# micro_schematic.net
KiCad netlist of a schematic drawn in Altium Designer
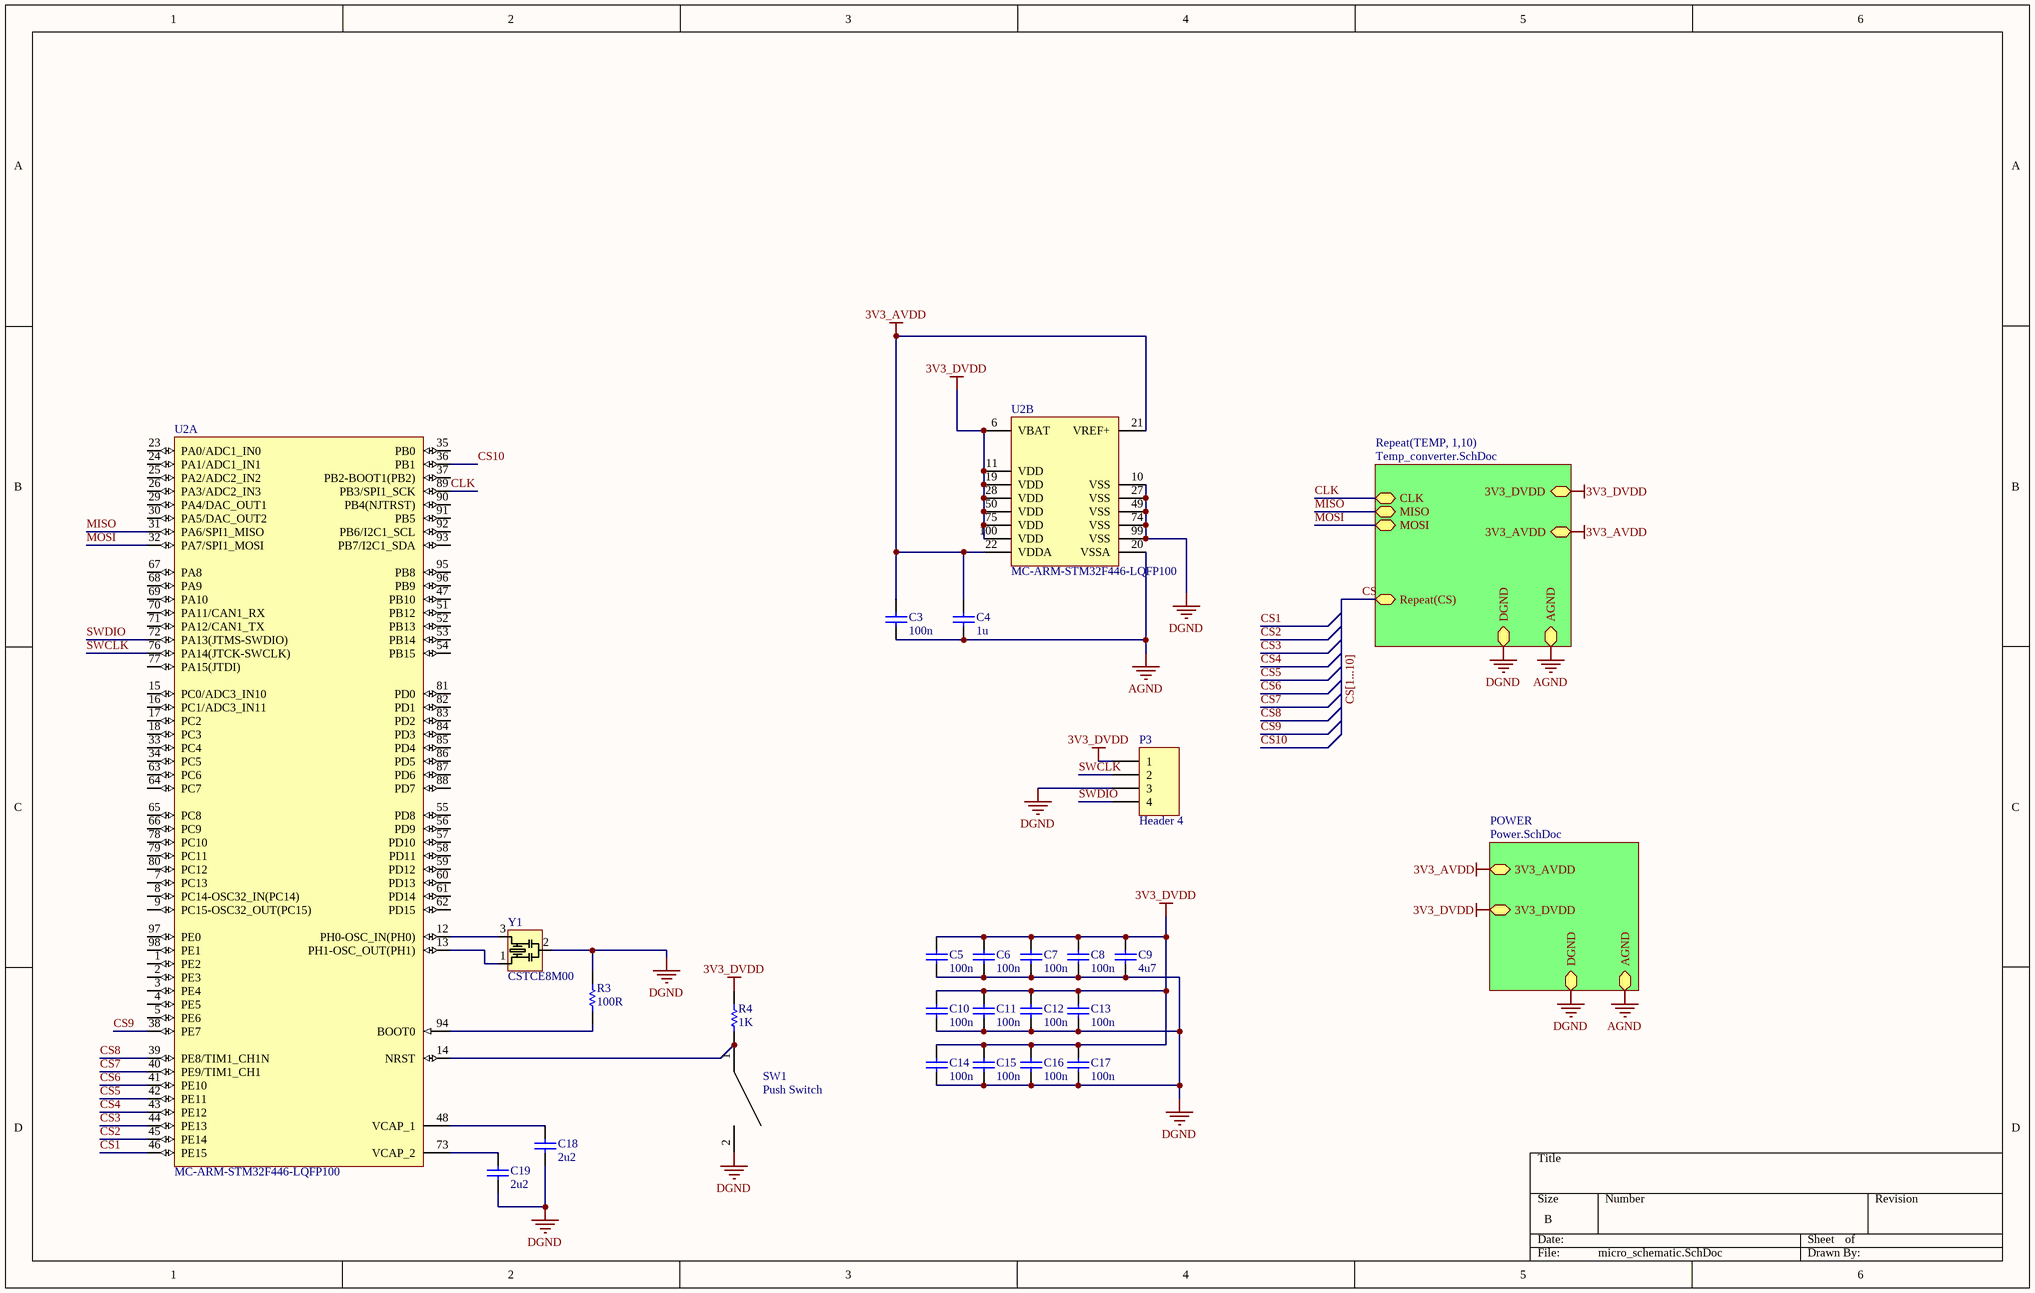
[diagram p0: micro_schematic.SchDoc]

(export (version "E")
  (design (tool "Eeschema 10.0.6"))
  (components
    (comp (ref "C3")
      (value "100n")
      (footprint "C0805")
      (description "0805 Capacitor")
      (libsource (lib "PARSEC1") (part "C0805"))
    )
    (comp (ref "C4")
      (value "1u")
      (footprint "C0805")
      (description "0805 Capacitor")
      (libsource (lib "PARSEC1") (part "C0805"))
    )
    (comp (ref "C5")
      (value "100n")
      (footprint "C0805")
      (description "0805 Capacitor")
      (libsource (lib "PARSEC1") (part "C0805"))
    )
    (comp (ref "C6")
      (value "100n")
      (footprint "C0805")
      (description "0805 Capacitor")
      (libsource (lib "PARSEC1") (part "C0805"))
    )
    (comp (ref "C7")
      (value "100n")
      (footprint "C0805")
      (description "0805 Capacitor")
      (libsource (lib "PARSEC1") (part "C0805"))
    )
    (comp (ref "C8")
      (value "100n")
      (footprint "C0805")
      (description "0805 Capacitor")
      (libsource (lib "PARSEC1") (part "C0805"))
    )
    (comp (ref "C9")
      (value "4u7")
      (footprint "C0805")
      (description "0805 Capacitor")
      (libsource (lib "PARSEC1") (part "C0805"))
    )
    (comp (ref "C10")
      (value "100n")
      (footprint "C0805")
      (description "0805 Capacitor")
      (libsource (lib "PARSEC1") (part "C0805"))
    )
    (comp (ref "C11")
      (value "100n")
      (footprint "C0805")
      (description "0805 Capacitor")
      (libsource (lib "PARSEC1") (part "C0805"))
    )
    (comp (ref "C12")
      (value "100n")
      (footprint "C0805")
      (description "0805 Capacitor")
      (libsource (lib "PARSEC1") (part "C0805"))
    )
    (comp (ref "C13")
      (value "100n")
      (footprint "C0805")
      (description "0805 Capacitor")
      (libsource (lib "PARSEC1") (part "C0805"))
    )
    (comp (ref "C14")
      (value "100n")
      (footprint "C0805")
      (description "0805 Capacitor")
      (libsource (lib "PARSEC1") (part "C0805"))
    )
    (comp (ref "C15")
      (value "100n")
      (footprint "C0805")
      (description "0805 Capacitor")
      (libsource (lib "PARSEC1") (part "C0805"))
    )
    (comp (ref "C16")
      (value "100n")
      (footprint "C0805")
      (description "0805 Capacitor")
      (libsource (lib "PARSEC1") (part "C0805"))
    )
    (comp (ref "C17")
      (value "100n")
      (footprint "C0805")
      (description "0805 Capacitor")
      (libsource (lib "PARSEC1") (part "C0805"))
    )
    (comp (ref "C18")
      (value "2u2")
      (footprint "C0805")
      (description "0805 Capacitor")
      (libsource (lib "PARSEC1") (part "C0805"))
    )
    (comp (ref "C19")
      (value "2u2")
      (footprint "C0805")
      (description "0805 Capacitor")
      (libsource (lib "PARSEC1") (part "C0805"))
    )
    (comp (ref "P3")
      (value "Header 4")
      (footprint "HDR1X4")
      (description "Header, 4-Pin")
      (fields (field (name "PUBLISHER") "Altium Limited"))
      (libsource (lib "Miscellaneous Connectors") (part "Header 4"))
    )
    (comp (ref "R3")
      (value "100R")
      (footprint "R0805")
      (description "RESISTOR 0805")
      (libsource (lib "PARSEC1") (part "R0805"))
    )
    (comp (ref "R4")
      (value "1K")
      (footprint "R0805")
      (description "RESISTOR 0805")
      (libsource (lib "PARSEC1") (part "R0805"))
    )
    (comp (ref "SW1")
      (value "Push Switch")
      (footprint "PUSHBUTTON")
      (libsource (lib "PARSEC") (part "PUSHBUTTON"))
    )
    (comp (ref "U2")
      (value "MC-ARM-STM32F446-LQFP100")
      (footprint "STM-LQFP100_N")
      (libsource (lib "PARSEC1") (part "MC-ARM-STM32F446-LQFP100"))
    )
    (comp (ref "Y1")
      (value "CSTCE8M00")
      (footprint "8MHz Ceramic Resonator")
      (description "8MHz Ceramic Resonator")
      (libsource (lib "PARSEC1") (part "CSTCE8M00"))
    )
  )
  (nets
    (net (code "2") (name "/CLK") (class "Default")
      (node (ref "U2") (pin "89") (pinfunction "PB3/SPI1_SCK_89") (pintype "bidirectional"))
    )
    (net (code "3") (name "/CS1") (class "Default")
      (node (ref "U2") (pin "46") (pinfunction "PE15_46") (pintype "bidirectional"))
    )
    (net (code "4") (name "/CS2") (class "Default")
      (node (ref "U2") (pin "45") (pinfunction "PE14_45") (pintype "bidirectional"))
    )
    (net (code "5") (name "/CS3") (class "Default")
      (node (ref "U2") (pin "44") (pinfunction "PE13_44") (pintype "bidirectional"))
    )
    (net (code "6") (name "/CS4") (class "Default")
      (node (ref "U2") (pin "43") (pinfunction "PE12_43") (pintype "bidirectional"))
    )
    (net (code "7") (name "/CS5") (class "Default")
      (node (ref "U2") (pin "42") (pinfunction "PE11_42") (pintype "bidirectional"))
    )
    (net (code "8") (name "/CS6") (class "Default")
      (node (ref "U2") (pin "41") (pinfunction "PE10_41") (pintype "bidirectional"))
    )
    (net (code "9") (name "/CS7") (class "Default")
      (node (ref "U2") (pin "40") (pinfunction "PE9/TIM1_CH1_40") (pintype "bidirectional"))
    )
    (net (code "10") (name "/CS8") (class "Default")
      (node (ref "U2") (pin "39") (pinfunction "PE8/TIM1_CH1N_39") (pintype "bidirectional"))
    )
    (net (code "11") (name "/CS9") (class "Default")
      (node (ref "U2") (pin "38") (pinfunction "PE7_38") (pintype "bidirectional"))
    )
    (net (code "12") (name "/CS10") (class "Default")
      (node (ref "U2") (pin "36") (pinfunction "PB1_36") (pintype "bidirectional"))
    )
    (net (code "13") (name "/MISO") (class "Default")
      (node (ref "U2") (pin "31") (pinfunction "PA6/SPI1_MISO_31") (pintype "bidirectional"))
    )
    (net (code "14") (name "/MOSI") (class "Default")
      (node (ref "U2") (pin "32") (pinfunction "PA7/SPI1_MOSI_32") (pintype "bidirectional"))
    )
    (net (code "15") (name "/SWCLK") (class "Default")
      (node (ref "P3") (pin "2") (pinfunction "2_2") (pintype "passive"))
      (node (ref "U2") (pin "76") (pinfunction "PA14(JTCK-SWCLK)_76") (pintype "bidirectional"))
    )
    (net (code "16") (name "/SWDIO") (class "Default")
      (node (ref "P3") (pin "4") (pinfunction "4_4") (pintype "passive"))
      (node (ref "U2") (pin "72") (pinfunction "PA13(JTMS-SWDIO)_72") (pintype "bidirectional"))
    )
    (net (code "18") (name "3V3_AVDD") (class "Default")
      (node (ref "C3") (pin "1") (pinfunction "1_1") (pintype "passive"))
      (node (ref "C4") (pin "1") (pinfunction "1_1") (pintype "passive"))
      (node (ref "U2") (pin "21") (pinfunction "VREF+_21") (pintype "power_in"))
      (node (ref "U2") (pin "22") (pinfunction "VDDA_22") (pintype "power_in"))
    )
    (net (code "19") (name "3V3_DVDD") (class "Default")
      (node (ref "C10") (pin "1") (pinfunction "1_1") (pintype "passive"))
      (node (ref "C11") (pin "1") (pinfunction "1_1") (pintype "passive"))
      (node (ref "C12") (pin "1") (pinfunction "1_1") (pintype "passive"))
      (node (ref "C13") (pin "1") (pinfunction "1_1") (pintype "passive"))
      (node (ref "C14") (pin "1") (pinfunction "1_1") (pintype "passive"))
      (node (ref "C15") (pin "1") (pinfunction "1_1") (pintype "passive"))
      (node (ref "C16") (pin "1") (pinfunction "1_1") (pintype "passive"))
      (node (ref "C17") (pin "1") (pinfunction "1_1") (pintype "passive"))
      (node (ref "C5") (pin "1") (pinfunction "1_1") (pintype "passive"))
      (node (ref "C6") (pin "1") (pinfunction "1_1") (pintype "passive"))
      (node (ref "C7") (pin "1") (pinfunction "1_1") (pintype "passive"))
      (node (ref "C8") (pin "1") (pinfunction "1_1") (pintype "passive"))
      (node (ref "C9") (pin "1") (pinfunction "1_1") (pintype "passive"))
      (node (ref "P3") (pin "1") (pinfunction "1_1") (pintype "passive"))
      (node (ref "R4") (pin "2") (pinfunction "2_2") (pintype "passive"))
      (node (ref "U2") (pin "100") (pinfunction "VDD_100") (pintype "power_in"))
      (node (ref "U2") (pin "11") (pinfunction "VDD_11") (pintype "power_in"))
      (node (ref "U2") (pin "19") (pinfunction "VDD_19") (pintype "power_in"))
      (node (ref "U2") (pin "28") (pinfunction "VDD_28") (pintype "power_in"))
      (node (ref "U2") (pin "50") (pinfunction "VDD_50") (pintype "power_in"))
      (node (ref "U2") (pin "6") (pinfunction "VBAT_6") (pintype "power_in"))
      (node (ref "U2") (pin "75") (pinfunction "VDD_75") (pintype "power_in"))
    )
    (net (code "20") (name "AGND") (class "Default")
      (node (ref "C3") (pin "2") (pinfunction "2_2") (pintype "passive"))
      (node (ref "C4") (pin "2") (pinfunction "2_2") (pintype "passive"))
      (node (ref "U2") (pin "20") (pinfunction "VSSA_20") (pintype "power_in"))
    )
    (net (code "21") (name "DGND") (class "Default")
      (node (ref "C10") (pin "2") (pinfunction "2_2") (pintype "passive"))
      (node (ref "C11") (pin "2") (pinfunction "2_2") (pintype "passive"))
      (node (ref "C12") (pin "2") (pinfunction "2_2") (pintype "passive"))
      (node (ref "C13") (pin "2") (pinfunction "2_2") (pintype "passive"))
      (node (ref "C14") (pin "2") (pinfunction "2_2") (pintype "passive"))
      (node (ref "C15") (pin "2") (pinfunction "2_2") (pintype "passive"))
      (node (ref "C16") (pin "2") (pinfunction "2_2") (pintype "passive"))
      (node (ref "C17") (pin "2") (pinfunction "2_2") (pintype "passive"))
      (node (ref "C18") (pin "2") (pinfunction "2_2") (pintype "passive"))
      (node (ref "C19") (pin "2") (pinfunction "2_2") (pintype "passive"))
      (node (ref "C5") (pin "2") (pinfunction "2_2") (pintype "passive"))
      (node (ref "C6") (pin "2") (pinfunction "2_2") (pintype "passive"))
      (node (ref "C7") (pin "2") (pinfunction "2_2") (pintype "passive"))
      (node (ref "C8") (pin "2") (pinfunction "2_2") (pintype "passive"))
      (node (ref "C9") (pin "2") (pinfunction "2_2") (pintype "passive"))
      (node (ref "P3") (pin "3") (pinfunction "3_3") (pintype "passive"))
      (node (ref "R3") (pin "2") (pinfunction "2_2") (pintype "passive"))
      (node (ref "SW1") (pin "2") (pinfunction "3_2") (pintype "passive"))
      (node (ref "U2") (pin "10") (pinfunction "VSS_10") (pintype "power_in"))
      (node (ref "U2") (pin "27") (pinfunction "VSS_27") (pintype "power_in"))
      (node (ref "U2") (pin "49") (pinfunction "VSS_49") (pintype "power_in"))
      (node (ref "U2") (pin "74") (pinfunction "VSS_74") (pintype "power_in"))
      (node (ref "U2") (pin "99") (pinfunction "VSS_99") (pintype "power_in"))
      (node (ref "Y1") (pin "2") (pinfunction "GND_2") (pintype "passive"))
    )
    (net (code "22") (name "Net-(SW1-2)") (class "Default")
      (node (ref "R4") (pin "1") (pinfunction "1_1") (pintype "passive"))
      (node (ref "SW1") (pin "1") (pinfunction "2_1") (pintype "passive"))
      (node (ref "U2") (pin "14") (pinfunction "NRST_14") (pintype "bidirectional"))
    )
    (net (code "23") (name "Net-(U2A-BOOT0)") (class "Default")
      (node (ref "R3") (pin "1") (pinfunction "1_1") (pintype "passive"))
      (node (ref "U2") (pin "94") (pinfunction "BOOT0_94") (pintype "input"))
    )
    (net (code "24") (name "Net-(U2A-PH0-OSC_IN(PH0))") (class "Default")
      (node (ref "U2") (pin "12") (pinfunction "PH0-OSC_IN(PH0)_12") (pintype "bidirectional"))
      (node (ref "Y1") (pin "3") (pinfunction "OSC2_3") (pintype "passive"))
    )
    (net (code "25") (name "Net-(U2A-PH1-OSC_OUT(PH1))") (class "Default")
      (node (ref "U2") (pin "13") (pinfunction "PH1-OSC_OUT(PH1)_13") (pintype "bidirectional"))
      (node (ref "Y1") (pin "1") (pinfunction "OSC1_1") (pintype "passive"))
    )
    (net (code "26") (name "Net-(U2A-VCAP_1)") (class "Default")
      (node (ref "C18") (pin "1") (pinfunction "1_1") (pintype "passive"))
      (node (ref "U2") (pin "48") (pinfunction "VCAP_1_48") (pintype "passive"))
    )
    (net (code "27") (name "Net-(U2A-VCAP_2)") (class "Default")
      (node (ref "C19") (pin "1") (pinfunction "1_1") (pintype "passive"))
      (node (ref "U2") (pin "73") (pinfunction "VCAP_2_73") (pintype "passive"))
    )
    (net (code "28") (name "unconnected-(U2A-PA0{slash}ADC1_IN0-Pad23)") (class "Default")
      (node (ref "U2") (pin "23") (pinfunction "PA0/ADC1_IN0_23") (pintype "bidirectional"))
    )
    (net (code "29") (name "unconnected-(U2A-PA1{slash}ADC1_IN1-Pad24)") (class "Default")
      (node (ref "U2") (pin "24") (pinfunction "PA1/ADC1_IN1_24") (pintype "bidirectional"))
    )
    (net (code "30") (name "unconnected-(U2A-PA2{slash}ADC2_IN2-Pad25)") (class "Default")
      (node (ref "U2") (pin "25") (pinfunction "PA2/ADC2_IN2_25") (pintype "bidirectional"))
    )
    (net (code "31") (name "unconnected-(U2A-PA3{slash}ADC2_IN3-Pad26)") (class "Default")
      (node (ref "U2") (pin "26") (pinfunction "PA3/ADC2_IN3_26") (pintype "bidirectional"))
    )
    (net (code "32") (name "unconnected-(U2A-PA4{slash}DAC_OUT1-Pad29)") (class "Default")
      (node (ref "U2") (pin "29") (pinfunction "PA4/DAC_OUT1_29") (pintype "bidirectional"))
    )
    (net (code "33") (name "unconnected-(U2A-PA5{slash}DAC_OUT2-Pad30)") (class "Default")
      (node (ref "U2") (pin "30") (pinfunction "PA5/DAC_OUT2_30") (pintype "bidirectional"))
    )
    (net (code "34") (name "unconnected-(U2A-PA8-Pad67)") (class "Default")
      (node (ref "U2") (pin "67") (pinfunction "PA8_67") (pintype "bidirectional"))
    )
    (net (code "35") (name "unconnected-(U2A-PA9-Pad68)") (class "Default")
      (node (ref "U2") (pin "68") (pinfunction "PA9_68") (pintype "bidirectional"))
    )
    (net (code "36") (name "unconnected-(U2A-PA10-Pad69)") (class "Default")
      (node (ref "U2") (pin "69") (pinfunction "PA10_69") (pintype "bidirectional"))
    )
    (net (code "37") (name "unconnected-(U2A-PA11{slash}CAN1_RX-Pad70)") (class "Default")
      (node (ref "U2") (pin "70") (pinfunction "PA11/CAN1_RX_70") (pintype "bidirectional"))
    )
    (net (code "38") (name "unconnected-(U2A-PA12{slash}CAN1_TX-Pad71)") (class "Default")
      (node (ref "U2") (pin "71") (pinfunction "PA12/CAN1_TX_71") (pintype "bidirectional"))
    )
    (net (code "39") (name "unconnected-(U2A-PA15(JTDI)-Pad77)") (class "Default")
      (node (ref "U2") (pin "77") (pinfunction "PA15(JTDI)_77") (pintype "bidirectional"))
    )
    (net (code "40") (name "unconnected-(U2A-PB0-Pad35)") (class "Default")
      (node (ref "U2") (pin "35") (pinfunction "PB0_35") (pintype "bidirectional"))
    )
    (net (code "41") (name "unconnected-(U2A-PB2-BOOT1(PB2)-Pad37)") (class "Default")
      (node (ref "U2") (pin "37") (pinfunction "PB2-BOOT1(PB2)_37") (pintype "bidirectional"))
    )
    (net (code "42") (name "unconnected-(U2A-PB4(NJTRST)-Pad90)") (class "Default")
      (node (ref "U2") (pin "90") (pinfunction "PB4(NJTRST)_90") (pintype "bidirectional"))
    )
    (net (code "43") (name "unconnected-(U2A-PB5-Pad91)") (class "Default")
      (node (ref "U2") (pin "91") (pinfunction "PB5_91") (pintype "bidirectional"))
    )
    (net (code "44") (name "unconnected-(U2A-PB6{slash}I2C1_SCL-Pad92)") (class "Default")
      (node (ref "U2") (pin "92") (pinfunction "PB6/I2C1_SCL_92") (pintype "bidirectional"))
    )
    (net (code "45") (name "unconnected-(U2A-PB7{slash}I2C1_SDA-Pad93)") (class "Default")
      (node (ref "U2") (pin "93") (pinfunction "PB7/I2C1_SDA_93") (pintype "bidirectional"))
    )
    (net (code "46") (name "unconnected-(U2A-PB8-Pad95)") (class "Default")
      (node (ref "U2") (pin "95") (pinfunction "PB8_95") (pintype "bidirectional"))
    )
    (net (code "47") (name "unconnected-(U2A-PB9-Pad96)") (class "Default")
      (node (ref "U2") (pin "96") (pinfunction "PB9_96") (pintype "bidirectional"))
    )
    (net (code "48") (name "unconnected-(U2A-PB10-Pad47)") (class "Default")
      (node (ref "U2") (pin "47") (pinfunction "PB10_47") (pintype "bidirectional"))
    )
    (net (code "49") (name "unconnected-(U2A-PB12-Pad51)") (class "Default")
      (node (ref "U2") (pin "51") (pinfunction "PB12_51") (pintype "bidirectional"))
    )
    (net (code "50") (name "unconnected-(U2A-PB13-Pad52)") (class "Default")
      (node (ref "U2") (pin "52") (pinfunction "PB13_52") (pintype "bidirectional"))
    )
    (net (code "51") (name "unconnected-(U2A-PB14-Pad53)") (class "Default")
      (node (ref "U2") (pin "53") (pinfunction "PB14_53") (pintype "bidirectional"))
    )
    (net (code "52") (name "unconnected-(U2A-PB15-Pad54)") (class "Default")
      (node (ref "U2") (pin "54") (pinfunction "PB15_54") (pintype "bidirectional"))
    )
    (net (code "53") (name "unconnected-(U2A-PC0{slash}ADC3_IN10-Pad15)") (class "Default")
      (node (ref "U2") (pin "15") (pinfunction "PC0/ADC3_IN10_15") (pintype "bidirectional"))
    )
    (net (code "54") (name "unconnected-(U2A-PC1{slash}ADC3_IN11-Pad16)") (class "Default")
      (node (ref "U2") (pin "16") (pinfunction "PC1/ADC3_IN11_16") (pintype "bidirectional"))
    )
    (net (code "55") (name "unconnected-(U2A-PC2-Pad17)") (class "Default")
      (node (ref "U2") (pin "17") (pinfunction "PC2_17") (pintype "bidirectional"))
    )
    (net (code "56") (name "unconnected-(U2A-PC3-Pad18)") (class "Default")
      (node (ref "U2") (pin "18") (pinfunction "PC3_18") (pintype "bidirectional"))
    )
    (net (code "57") (name "unconnected-(U2A-PC4-Pad33)") (class "Default")
      (node (ref "U2") (pin "33") (pinfunction "PC4_33") (pintype "bidirectional"))
    )
    (net (code "58") (name "unconnected-(U2A-PC5-Pad34)") (class "Default")
      (node (ref "U2") (pin "34") (pinfunction "PC5_34") (pintype "bidirectional"))
    )
    (net (code "59") (name "unconnected-(U2A-PC6-Pad63)") (class "Default")
      (node (ref "U2") (pin "63") (pinfunction "PC6_63") (pintype "bidirectional"))
    )
    (net (code "60") (name "unconnected-(U2A-PC7-Pad64)") (class "Default")
      (node (ref "U2") (pin "64") (pinfunction "PC7_64") (pintype "bidirectional"))
    )
    (net (code "61") (name "unconnected-(U2A-PC8-Pad65)") (class "Default")
      (node (ref "U2") (pin "65") (pinfunction "PC8_65") (pintype "bidirectional"))
    )
    (net (code "62") (name "unconnected-(U2A-PC9-Pad66)") (class "Default")
      (node (ref "U2") (pin "66") (pinfunction "PC9_66") (pintype "bidirectional"))
    )
    (net (code "63") (name "unconnected-(U2A-PC10-Pad78)") (class "Default")
      (node (ref "U2") (pin "78") (pinfunction "PC10_78") (pintype "bidirectional"))
    )
    (net (code "64") (name "unconnected-(U2A-PC11-Pad79)") (class "Default")
      (node (ref "U2") (pin "79") (pinfunction "PC11_79") (pintype "bidirectional"))
    )
    (net (code "65") (name "unconnected-(U2A-PC12-Pad80)") (class "Default")
      (node (ref "U2") (pin "80") (pinfunction "PC12_80") (pintype "bidirectional"))
    )
    (net (code "66") (name "unconnected-(U2A-PC13-Pad7)") (class "Default")
      (node (ref "U2") (pin "7") (pinfunction "PC13_7") (pintype "bidirectional"))
    )
    (net (code "67") (name "unconnected-(U2A-PC14-OSC32_IN(PC14)-Pad8)") (class "Default")
      (node (ref "U2") (pin "8") (pinfunction "PC14-OSC32_IN(PC14)_8") (pintype "bidirectional"))
    )
    (net (code "68") (name "unconnected-(U2A-PC15-OSC32_OUT(PC15)-Pad9)") (class "Default")
      (node (ref "U2") (pin "9") (pinfunction "PC15-OSC32_OUT(PC15)_9") (pintype "bidirectional"))
    )
    (net (code "69") (name "unconnected-(U2A-PD0-Pad81)") (class "Default")
      (node (ref "U2") (pin "81") (pinfunction "PD0_81") (pintype "bidirectional"))
    )
    (net (code "70") (name "unconnected-(U2A-PD1-Pad82)") (class "Default")
      (node (ref "U2") (pin "82") (pinfunction "PD1_82") (pintype "bidirectional"))
    )
    (net (code "71") (name "unconnected-(U2A-PD2-Pad83)") (class "Default")
      (node (ref "U2") (pin "83") (pinfunction "PD2_83") (pintype "bidirectional"))
    )
    (net (code "72") (name "unconnected-(U2A-PD3-Pad84)") (class "Default")
      (node (ref "U2") (pin "84") (pinfunction "PD3_84") (pintype "bidirectional"))
    )
    (net (code "73") (name "unconnected-(U2A-PD4-Pad85)") (class "Default")
      (node (ref "U2") (pin "85") (pinfunction "PD4_85") (pintype "bidirectional"))
    )
    (net (code "74") (name "unconnected-(U2A-PD5-Pad86)") (class "Default")
      (node (ref "U2") (pin "86") (pinfunction "PD5_86") (pintype "bidirectional"))
    )
    (net (code "75") (name "unconnected-(U2A-PD6-Pad87)") (class "Default")
      (node (ref "U2") (pin "87") (pinfunction "PD6_87") (pintype "bidirectional"))
    )
    (net (code "76") (name "unconnected-(U2A-PD7-Pad88)") (class "Default")
      (node (ref "U2") (pin "88") (pinfunction "PD7_88") (pintype "bidirectional"))
    )
    (net (code "77") (name "unconnected-(U2A-PD8-Pad55)") (class "Default")
      (node (ref "U2") (pin "55") (pinfunction "PD8_55") (pintype "bidirectional"))
    )
    (net (code "78") (name "unconnected-(U2A-PD9-Pad56)") (class "Default")
      (node (ref "U2") (pin "56") (pinfunction "PD9_56") (pintype "bidirectional"))
    )
    (net (code "79") (name "unconnected-(U2A-PD10-Pad57)") (class "Default")
      (node (ref "U2") (pin "57") (pinfunction "PD10_57") (pintype "bidirectional"))
    )
    (net (code "80") (name "unconnected-(U2A-PD11-Pad58)") (class "Default")
      (node (ref "U2") (pin "58") (pinfunction "PD11_58") (pintype "bidirectional"))
    )
    (net (code "81") (name "unconnected-(U2A-PD12-Pad59)") (class "Default")
      (node (ref "U2") (pin "59") (pinfunction "PD12_59") (pintype "bidirectional"))
    )
    (net (code "82") (name "unconnected-(U2A-PD13-Pad60)") (class "Default")
      (node (ref "U2") (pin "60") (pinfunction "PD13_60") (pintype "bidirectional"))
    )
    (net (code "83") (name "unconnected-(U2A-PD14-Pad61)") (class "Default")
      (node (ref "U2") (pin "61") (pinfunction "PD14_61") (pintype "bidirectional"))
    )
    (net (code "84") (name "unconnected-(U2A-PD15-Pad62)") (class "Default")
      (node (ref "U2") (pin "62") (pinfunction "PD15_62") (pintype "bidirectional"))
    )
    (net (code "85") (name "unconnected-(U2A-PE0-Pad97)") (class "Default")
      (node (ref "U2") (pin "97") (pinfunction "PE0_97") (pintype "bidirectional"))
    )
    (net (code "86") (name "unconnected-(U2A-PE1-Pad98)") (class "Default")
      (node (ref "U2") (pin "98") (pinfunction "PE1_98") (pintype "bidirectional"))
    )
    (net (code "87") (name "unconnected-(U2A-PE2-Pad1)") (class "Default")
      (node (ref "U2") (pin "1") (pinfunction "PE2_1") (pintype "bidirectional"))
    )
    (net (code "88") (name "unconnected-(U2A-PE3-Pad2)") (class "Default")
      (node (ref "U2") (pin "2") (pinfunction "PE3_2") (pintype "bidirectional"))
    )
    (net (code "89") (name "unconnected-(U2A-PE4-Pad3)") (class "Default")
      (node (ref "U2") (pin "3") (pinfunction "PE4_3") (pintype "bidirectional"))
    )
    (net (code "90") (name "unconnected-(U2A-PE5-Pad4)") (class "Default")
      (node (ref "U2") (pin "4") (pinfunction "PE5_4") (pintype "bidirectional"))
    )
    (net (code "91") (name "unconnected-(U2A-PE6-Pad5)") (class "Default")
      (node (ref "U2") (pin "5") (pinfunction "PE6_5") (pintype "bidirectional"))
    )
  )
)
